# ai_breakout_ft232RL.net
KiCad netlist of a schematic drawn in EAGLE
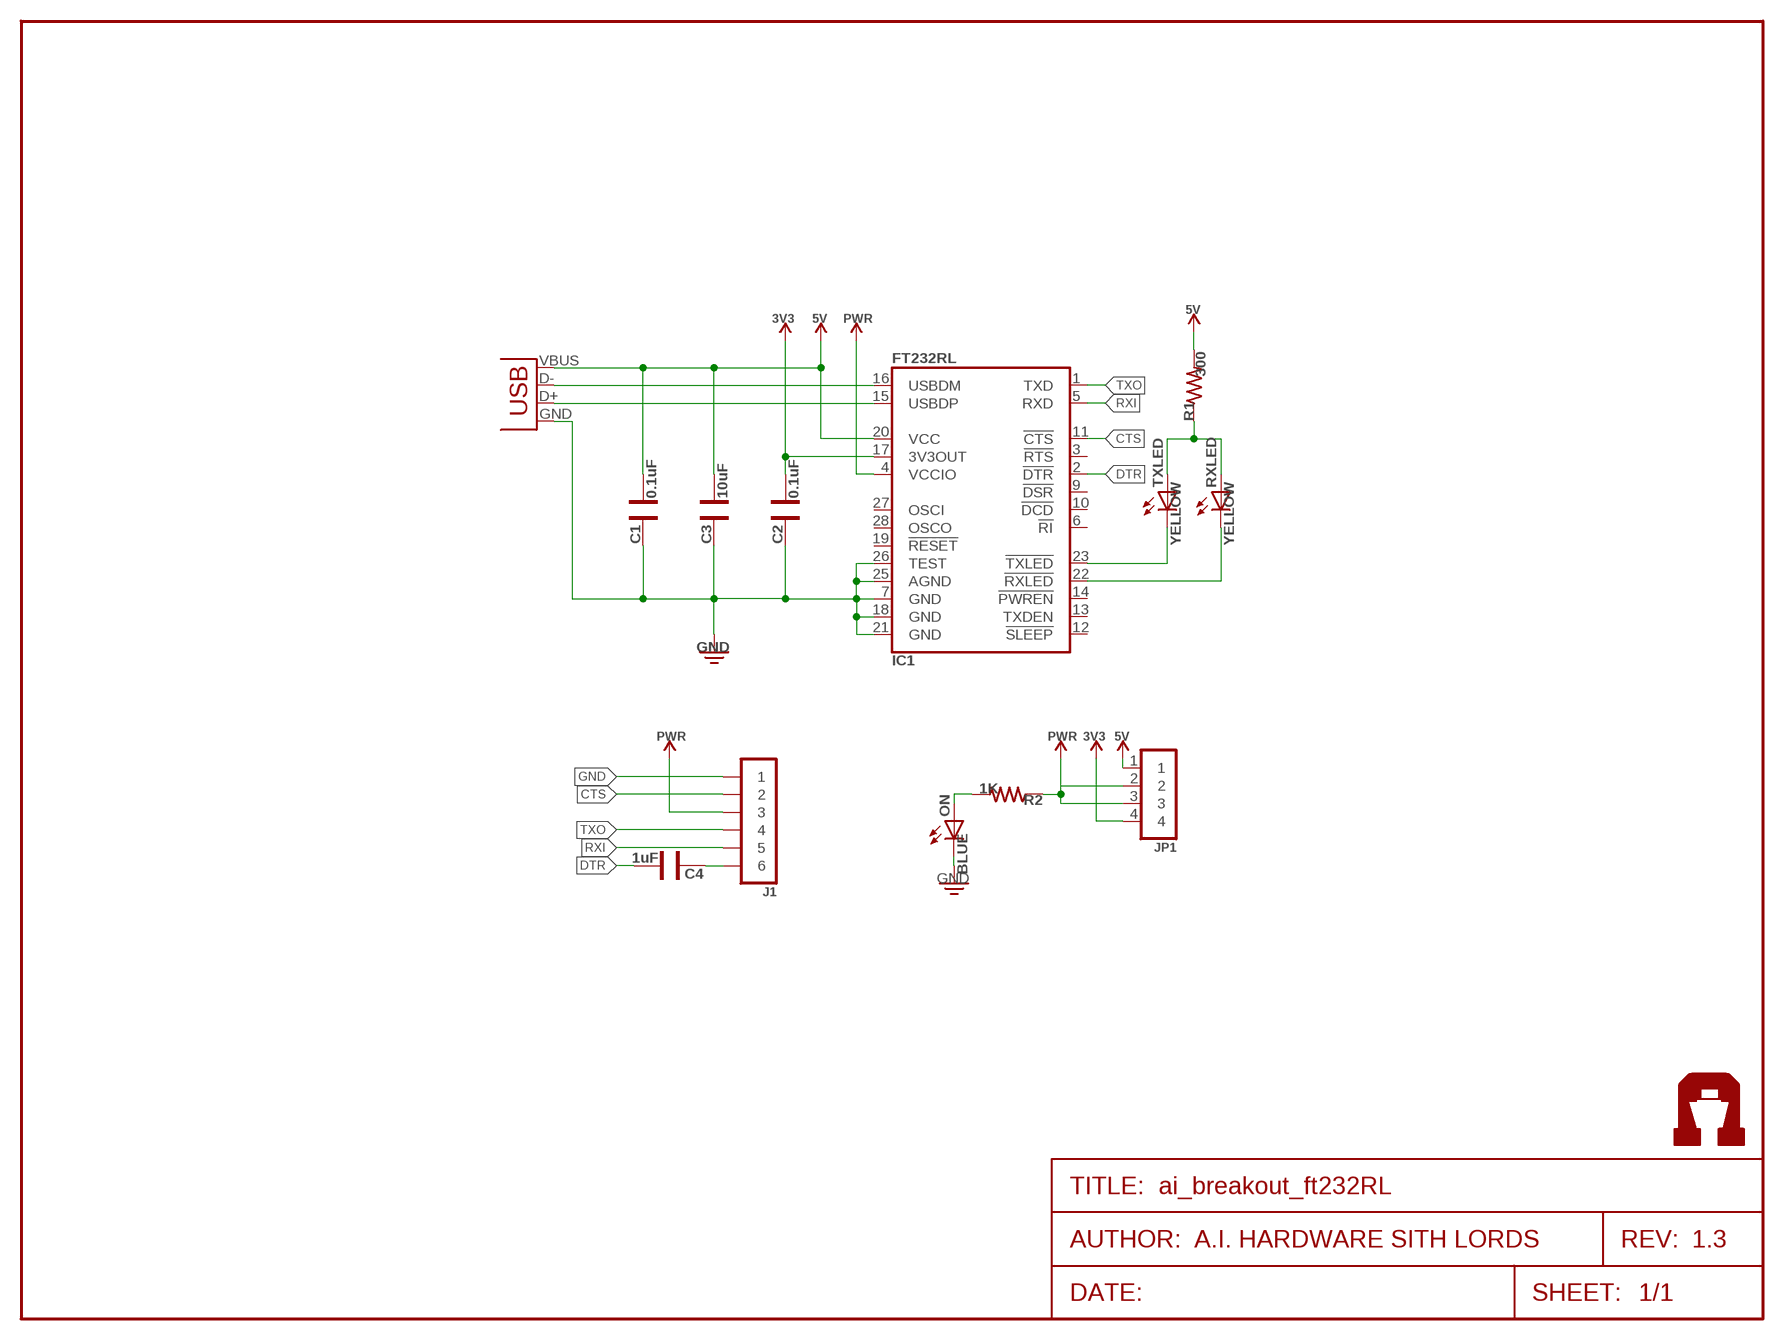
[diagram p0: schematic, sheet 1]

(export (version "E")
  (design (tool "Eeschema 10.0.6"))
  (components
    (comp (ref "C1")
      (value "0.1uF")
      (footprint "eagle-import:CAP-0603")
      (libsource (lib "eagle-import") (part "CAP0603"))
    )
    (comp (ref "C2")
      (value "0.1uF")
      (footprint "eagle-import:CAP-0603")
      (libsource (lib "eagle-import") (part "CAP0603"))
    )
    (comp (ref "C3")
      (value "10uF")
      (footprint "eagle-import:CAP-0603")
      (libsource (lib "eagle-import") (part "CAP0603"))
    )
    (comp (ref "C4")
      (value "1uF")
      (footprint "eagle-import:CAP-0603")
      (libsource (lib "eagle-import") (part "CAP0603"))
    )
    (comp (ref "IC1")
      (value "FT2332RL")
      (footprint "eagle-import:SSOP28-LD")
      (libsource (lib "eagle-import") (part "FT2332RL"))
    )
    (comp (ref "J1")
      (value "1X06LONG")
      (footprint "eagle-import:1X06-LONG")
      (libsource (lib "eagle-import") (part "1X06LONG"))
    )
    (comp (ref "JP1")
      (value "1X04NOSILK")
      (footprint "eagle-import:1X04-NOSILK")
      (libsource (lib "eagle-import") (part "1X04NOSILK"))
    )
    (comp (ref "ON")
      (value "BLUE")
      (footprint "eagle-import:LED-0603")
      (libsource (lib "eagle-import") (part "LED0603"))
    )
    (comp (ref "R1")
      (value "300")
      (footprint "eagle-import:RES-0603")
      (libsource (lib "eagle-import") (part "RES0603"))
    )
    (comp (ref "R2")
      (value "1K")
      (footprint "eagle-import:RES-0603")
      (libsource (lib "eagle-import") (part "RES0603"))
    )
    (comp (ref "RXLED")
      (value "YELLOW")
      (footprint "eagle-import:LED-0603")
      (libsource (lib "eagle-import") (part "LED0603"))
    )
    (comp (ref "TXLED")
      (value "YELLOW")
      (footprint "eagle-import:LED-0603")
      (libsource (lib "eagle-import") (part "LED0603"))
    )
    (comp (ref "U$3")
      (value "AI-LOGOL")
      (footprint "eagle-import:AI-LOGO-L")
      (libsource (lib "eagle-import") (part "AI-LOGOL"))
    )
    (comp (ref "USB1")
      (value "USBMICROB-TH")
      (footprint "eagle-import:USB-MICROB-TH")
      (libsource (lib "eagle-import") (part "USBMICROB-TH"))
    )
  )
  (nets
    (net (code "1") (name "3V3") (class "Default")
      (node (ref "C2") (pin "1") (pinfunction "1_1") (pintype "passive"))
      (node (ref "IC1") (pin "17") (pinfunction "3V3OUT_17") (pintype "power_in"))
      (node (ref "JP1") (pin "4") (pinfunction "4_4") (pintype "bidirectional"))
    )
    (net (code "2") (name "5V") (class "Default")
      (node (ref "C1") (pin "1") (pinfunction "1_1") (pintype "passive"))
      (node (ref "C3") (pin "1") (pinfunction "1_1") (pintype "passive"))
      (node (ref "IC1") (pin "20") (pinfunction "VCC_20") (pintype "power_in"))
      (node (ref "JP1") (pin "1") (pinfunction "1_1") (pintype "bidirectional"))
      (node (ref "R1") (pin "2") (pinfunction "2_2") (pintype "passive"))
      (node (ref "USB1") (pin "VBUS") (pinfunction "VBUS_VBUS") (pintype "bidirectional"))
    )
    (net (code "3") (name "CTS") (class "Default")
      (node (ref "IC1") (pin "11") (pinfunction "~{CTS}_11") (pintype "input"))
      (node (ref "J1") (pin "2") (pinfunction "2_2") (pintype "bidirectional"))
    )
    (net (code "4") (name "DTR") (class "Default")
      (node (ref "C4") (pin "1") (pinfunction "1_1") (pintype "passive"))
      (node (ref "IC1") (pin "2") (pinfunction "~{DTR}_2") (pintype "output"))
    )
    (net (code "5") (name "GND") (class "Default")
      (node (ref "C1") (pin "2") (pinfunction "2_2") (pintype "passive"))
      (node (ref "C2") (pin "2") (pinfunction "2_2") (pintype "passive"))
      (node (ref "C3") (pin "2") (pinfunction "2_2") (pintype "passive"))
      (node (ref "IC1") (pin "18") (pinfunction "GND_18") (pintype "power_in"))
      (node (ref "IC1") (pin "21") (pinfunction "GND_21") (pintype "power_in"))
      (node (ref "IC1") (pin "25") (pinfunction "AGND_25") (pintype "power_in"))
      (node (ref "IC1") (pin "26") (pinfunction "TEST_26") (pintype "input"))
      (node (ref "IC1") (pin "7") (pinfunction "GND_7") (pintype "power_in"))
      (node (ref "J1") (pin "1") (pinfunction "1_1") (pintype "bidirectional"))
      (node (ref "ON") (pin "C") (pinfunction "C_C") (pintype "passive"))
      (node (ref "USB1") (pin "GND") (pinfunction "GND_GND") (pintype "bidirectional"))
    )
    (net (code "6") (name "Net-(C4-Pad2)") (class "Default")
      (node (ref "C4") (pin "2") (pinfunction "2_2") (pintype "passive"))
      (node (ref "J1") (pin "6") (pinfunction "6_6") (pintype "bidirectional"))
    )
    (net (code "7") (name "Net-(IC1-USBDM)") (class "Default")
      (node (ref "IC1") (pin "16") (pinfunction "USBDM_16") (pintype "bidirectional"))
      (node (ref "USB1") (pin "D-") (pinfunction "D-_D-") (pintype "bidirectional"))
    )
    (net (code "8") (name "Net-(IC1-USBDP)") (class "Default")
      (node (ref "IC1") (pin "15") (pinfunction "USBDP_15") (pintype "bidirectional"))
      (node (ref "USB1") (pin "D+") (pinfunction "D+_D+") (pintype "bidirectional"))
    )
    (net (code "9") (name "Net-(IC1-~{RXLED})") (class "Default")
      (node (ref "IC1") (pin "22") (pinfunction "~{RXLED}_22") (pintype "input"))
      (node (ref "RXLED") (pin "C") (pinfunction "C_C") (pintype "passive"))
    )
    (net (code "10") (name "Net-(IC1-~{TXLED})") (class "Default")
      (node (ref "IC1") (pin "23") (pinfunction "~{TXLED}_23") (pintype "input"))
      (node (ref "TXLED") (pin "C") (pinfunction "C_C") (pintype "passive"))
    )
    (net (code "11") (name "Net-(ON-PadA)") (class "Default")
      (node (ref "ON") (pin "A") (pinfunction "A_A") (pintype "passive"))
      (node (ref "R2") (pin "2") (pinfunction "2_2") (pintype "passive"))
    )
    (net (code "12") (name "Net-(R1-Pad1)") (class "Default")
      (node (ref "R1") (pin "1") (pinfunction "1_1") (pintype "passive"))
      (node (ref "RXLED") (pin "A") (pinfunction "A_A") (pintype "passive"))
      (node (ref "TXLED") (pin "A") (pinfunction "A_A") (pintype "passive"))
    )
    (net (code "13") (name "PWR") (class "Default")
      (node (ref "IC1") (pin "4") (pinfunction "VCCIO_4") (pintype "power_in"))
      (node (ref "J1") (pin "3") (pinfunction "3_3") (pintype "bidirectional"))
      (node (ref "JP1") (pin "2") (pinfunction "2_2") (pintype "bidirectional"))
      (node (ref "JP1") (pin "3") (pinfunction "3_3") (pintype "bidirectional"))
      (node (ref "R2") (pin "1") (pinfunction "1_1") (pintype "passive"))
    )
    (net (code "14") (name "RXI") (class "Default")
      (node (ref "IC1") (pin "5") (pinfunction "RXD_5") (pintype "input"))
      (node (ref "J1") (pin "5") (pinfunction "5_5") (pintype "bidirectional"))
    )
    (net (code "15") (name "TXO") (class "Default")
      (node (ref "IC1") (pin "1") (pinfunction "TXD_1") (pintype "output"))
      (node (ref "J1") (pin "4") (pinfunction "4_4") (pintype "bidirectional"))
    )
    (net (code "16") (name "unconnected-(IC1-OSCI-Pad27)") (class "Default")
      (node (ref "IC1") (pin "27") (pinfunction "OSCI_27") (pintype "no_connect"))
    )
    (net (code "17") (name "unconnected-(IC1-OSCO-Pad28)") (class "Default")
      (node (ref "IC1") (pin "28") (pinfunction "OSCO_28") (pintype "output"))
    )
    (net (code "18") (name "unconnected-(IC1-TXDEN-Pad13)") (class "Default")
      (node (ref "IC1") (pin "13") (pinfunction "TXDEN_13") (pintype "no_connect"))
    )
    (net (code "19") (name "unconnected-(IC1-~{DCD}-Pad10)") (class "Default")
      (node (ref "IC1") (pin "10") (pinfunction "~{DCD}_10") (pintype "no_connect"))
    )
    (net (code "20") (name "unconnected-(IC1-~{DSR}-Pad9)") (class "Default")
      (node (ref "IC1") (pin "9") (pinfunction "~{DSR}_9") (pintype "no_connect"))
    )
    (net (code "21") (name "unconnected-(IC1-~{PWREN}-Pad14)") (class "Default")
      (node (ref "IC1") (pin "14") (pinfunction "~{PWREN}_14") (pintype "no_connect"))
    )
    (net (code "22") (name "unconnected-(IC1-~{RESET}-Pad19)") (class "Default")
      (node (ref "IC1") (pin "19") (pinfunction "~{RESET}_19") (pintype "no_connect"))
    )
    (net (code "23") (name "unconnected-(IC1-~{RI}-Pad6)") (class "Default")
      (node (ref "IC1") (pin "6") (pinfunction "~{RI}_6") (pintype "no_connect"))
    )
    (net (code "24") (name "unconnected-(IC1-~{RTS}-Pad3)") (class "Default")
      (node (ref "IC1") (pin "3") (pinfunction "~{RTS}_3") (pintype "output"))
    )
    (net (code "25") (name "unconnected-(IC1-~{SLEEP}-Pad12)") (class "Default")
      (node (ref "IC1") (pin "12") (pinfunction "~{SLEEP}_12") (pintype "no_connect"))
    )
  )
)
